# EXM_Relay_Four_-_Rev_A1.net
KiCad netlist of a schematic drawn in EAGLE
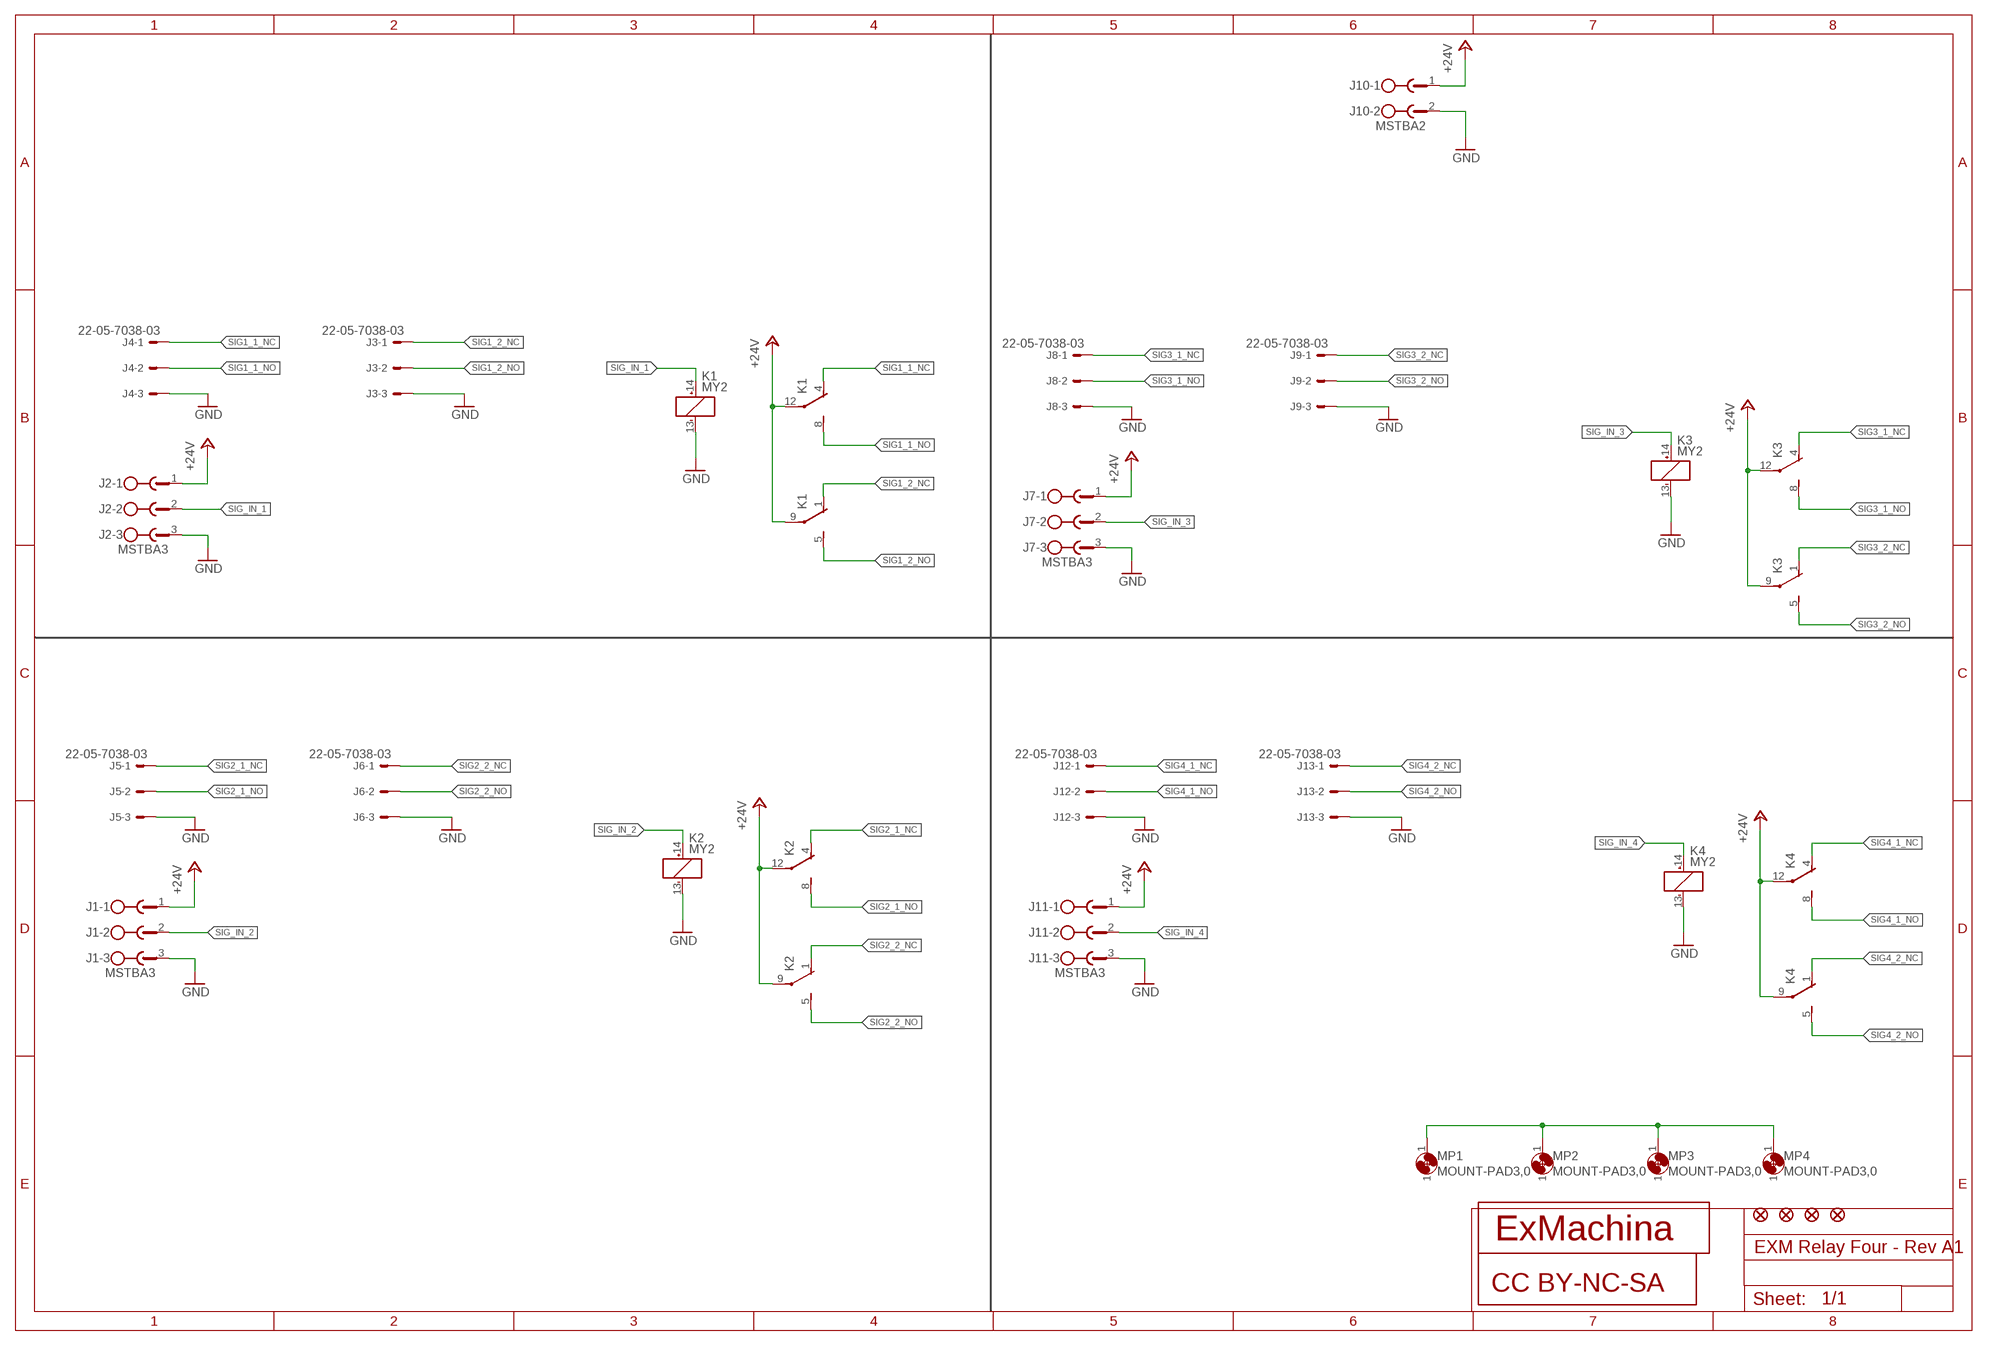
[diagram p0: schematic, sheet 1]

(export (version "E")
  (design (tool "Eeschema 10.0.6"))
  (components
    (comp (ref "CC1")
      (value "CC-BY-NC-SA")
      (footprint "eagle-import:CC-BY-NC-SA")
      (libsource (lib "eagle-import") (part "CC-BY-NC-SA"))
    )
    (comp (ref "J1")
      (value "MSTBA3")
      (footprint "eagle-import:MSTBA3")
      (fields (field (name "MF") "FARNELL") (field (name "MPN") "1757255"))
      (libsource (lib "eagle-import") (part "MSTBA3"))
    )
    (comp (ref "J2")
      (value "MSTBA3")
      (footprint "eagle-import:MSTBA3")
      (fields (field (name "MF") "FARNELL") (field (name "MPN") "1757255"))
      (libsource (lib "eagle-import") (part "MSTBA3"))
    )
    (comp (ref "J3")
      (value "22-05-7038-03")
      (footprint "eagle-import:7395-03")
      (libsource (lib "eagle-import") (part "22-?-0305-7038"))
    )
    (comp (ref "J4")
      (value "22-05-7038-03")
      (footprint "eagle-import:7395-03")
      (libsource (lib "eagle-import") (part "22-?-0305-7038"))
    )
    (comp (ref "J5")
      (value "22-05-7038-03")
      (footprint "eagle-import:7395-03")
      (libsource (lib "eagle-import") (part "22-?-0305-7038"))
    )
    (comp (ref "J6")
      (value "22-05-7038-03")
      (footprint "eagle-import:7395-03")
      (libsource (lib "eagle-import") (part "22-?-0305-7038"))
    )
    (comp (ref "J7")
      (value "MSTBA3")
      (footprint "eagle-import:MSTBA3")
      (fields (field (name "MF") "FARNELL") (field (name "MPN") "1757255"))
      (libsource (lib "eagle-import") (part "MSTBA3"))
    )
    (comp (ref "J8")
      (value "22-05-7038-03")
      (footprint "eagle-import:7395-03")
      (libsource (lib "eagle-import") (part "22-?-0305-7038"))
    )
    (comp (ref "J9")
      (value "22-05-7038-03")
      (footprint "eagle-import:7395-03")
      (libsource (lib "eagle-import") (part "22-?-0305-7038"))
    )
    (comp (ref "J10")
      (value "MSTBA2")
      (footprint "eagle-import:MSTBA2")
      (fields (field (name "MF") "FARNELL") (field (name "MPN") "1757242"))
      (libsource (lib "eagle-import") (part "MSTBA2"))
    )
    (comp (ref "J11")
      (value "MSTBA3")
      (footprint "eagle-import:MSTBA3")
      (fields (field (name "MF") "FARNELL") (field (name "MPN") "1757255"))
      (libsource (lib "eagle-import") (part "MSTBA3"))
    )
    (comp (ref "J12")
      (value "22-05-7038-03")
      (footprint "eagle-import:7395-03")
      (libsource (lib "eagle-import") (part "22-?-0305-7038"))
    )
    (comp (ref "J13")
      (value "22-05-7038-03")
      (footprint "eagle-import:7395-03")
      (libsource (lib "eagle-import") (part "22-?-0305-7038"))
    )
    (comp (ref "JP1")
      (value "FIDUCIAL1X2")
      (footprint "eagle-import:FIDUCIAL-1X2")
      (libsource (lib "eagle-import") (part "FIDUCIAL1X2"))
    )
    (comp (ref "JP2")
      (value "FIDUCIAL1X2")
      (footprint "eagle-import:FIDUCIAL-1X2")
      (libsource (lib "eagle-import") (part "FIDUCIAL1X2"))
    )
    (comp (ref "JP3")
      (value "FIDUCIAL1X2")
      (footprint "eagle-import:FIDUCIAL-1X2")
      (libsource (lib "eagle-import") (part "FIDUCIAL1X2"))
    )
    (comp (ref "JP4")
      (value "FIDUCIAL1X2")
      (footprint "eagle-import:FIDUCIAL-1X2")
      (libsource (lib "eagle-import") (part "FIDUCIAL1X2"))
    )
    (comp (ref "K1")
      (value "MY2")
      (footprint "eagle-import:PY08")
      (libsource (lib "eagle-import") (part "MY2"))
    )
    (comp (ref "K2")
      (value "MY2")
      (footprint "eagle-import:PY08")
      (libsource (lib "eagle-import") (part "MY2"))
    )
    (comp (ref "K3")
      (value "MY2")
      (footprint "eagle-import:PY08")
      (libsource (lib "eagle-import") (part "MY2"))
    )
    (comp (ref "K4")
      (value "MY2")
      (footprint "eagle-import:PY08")
      (libsource (lib "eagle-import") (part "MY2"))
    )
    (comp (ref "MP1")
      (value "MOUNT-PAD3,0")
      (footprint "eagle-import:P3,0")
      (libsource (lib "eagle-import") (part "MOUNT-PAD3,0"))
    )
    (comp (ref "MP2")
      (value "MOUNT-PAD3,0")
      (footprint "eagle-import:P3,0")
      (libsource (lib "eagle-import") (part "MOUNT-PAD3,0"))
    )
    (comp (ref "MP3")
      (value "MOUNT-PAD3,0")
      (footprint "eagle-import:P3,0")
      (libsource (lib "eagle-import") (part "MOUNT-PAD3,0"))
    )
    (comp (ref "MP4")
      (value "MOUNT-PAD3,0")
      (footprint "eagle-import:P3,0")
      (libsource (lib "eagle-import") (part "MOUNT-PAD3,0"))
    )
    (comp (ref "T1")
      (value "EXMACHINA-LOGO-NAME")
      (footprint "eagle-import:EXM-LOGO-BASELINE")
      (libsource (lib "eagle-import") (part "EXMACHINA-LOGO-NAME"))
    )
  )
  (nets
    (net (code "1") (name "+24V") (class "Default")
      (node (ref "J1") (pin "1") (pinfunction "1_1") (pintype "passive"))
      (node (ref "J10") (pin "1") (pinfunction "1_1") (pintype "passive"))
      (node (ref "J11") (pin "1") (pinfunction "1_1") (pintype "passive"))
      (node (ref "J2") (pin "1") (pinfunction "1_1") (pintype "passive"))
      (node (ref "J7") (pin "1") (pinfunction "1_1") (pintype "passive"))
      (node (ref "K1") (pin "12") (pinfunction "C_12") (pintype "passive"))
      (node (ref "K1") (pin "9") (pinfunction "C_9") (pintype "passive"))
      (node (ref "K2") (pin "12") (pinfunction "C_12") (pintype "passive"))
      (node (ref "K2") (pin "9") (pinfunction "C_9") (pintype "passive"))
      (node (ref "K3") (pin "12") (pinfunction "C_12") (pintype "passive"))
      (node (ref "K3") (pin "9") (pinfunction "C_9") (pintype "passive"))
      (node (ref "K4") (pin "12") (pinfunction "C_12") (pintype "passive"))
      (node (ref "K4") (pin "9") (pinfunction "C_9") (pintype "passive"))
    )
    (net (code "2") (name "GND") (class "Default")
      (node (ref "J1") (pin "3") (pinfunction "1_3") (pintype "passive"))
      (node (ref "J10") (pin "2") (pinfunction "1_2") (pintype "passive"))
      (node (ref "J11") (pin "3") (pinfunction "1_3") (pintype "passive"))
      (node (ref "J12") (pin "3") (pinfunction "S_3") (pintype "passive"))
      (node (ref "J13") (pin "3") (pinfunction "S_3") (pintype "passive"))
      (node (ref "J2") (pin "3") (pinfunction "1_3") (pintype "passive"))
      (node (ref "J3") (pin "3") (pinfunction "S_3") (pintype "passive"))
      (node (ref "J4") (pin "3") (pinfunction "S_3") (pintype "passive"))
      (node (ref "J5") (pin "3") (pinfunction "S_3") (pintype "passive"))
      (node (ref "J6") (pin "3") (pinfunction "S_3") (pintype "passive"))
      (node (ref "J7") (pin "3") (pinfunction "1_3") (pintype "passive"))
      (node (ref "J8") (pin "3") (pinfunction "S_3") (pintype "passive"))
      (node (ref "J9") (pin "3") (pinfunction "S_3") (pintype "passive"))
      (node (ref "K1") (pin "13") (pinfunction "-_13") (pintype "passive"))
      (node (ref "K2") (pin "13") (pinfunction "-_13") (pintype "passive"))
      (node (ref "K3") (pin "13") (pinfunction "-_13") (pintype "passive"))
      (node (ref "K4") (pin "13") (pinfunction "-_13") (pintype "passive"))
    )
    (net (code "3") (name "MOUNT-PAD3,0") (class "Default")
      (node (ref "MP1") (pin "1") (pinfunction "1_1") (pintype "power_in"))
      (node (ref "MP2") (pin "1") (pinfunction "1_1") (pintype "power_in"))
      (node (ref "MP3") (pin "1") (pinfunction "1_1") (pintype "power_in"))
      (node (ref "MP4") (pin "1") (pinfunction "1_1") (pintype "power_in"))
    )
    (net (code "4") (name "SIG1_1_NC") (class "Default")
      (node (ref "J4") (pin "1") (pinfunction "S_1") (pintype "passive"))
      (node (ref "K1") (pin "4") (pinfunction "NC_4") (pintype "passive"))
    )
    (net (code "5") (name "SIG1_1_NO") (class "Default")
      (node (ref "J4") (pin "2") (pinfunction "S_2") (pintype "passive"))
      (node (ref "K1") (pin "8") (pinfunction "NO_8") (pintype "passive"))
    )
    (net (code "6") (name "SIG1_2_NC") (class "Default")
      (node (ref "J3") (pin "1") (pinfunction "S_1") (pintype "passive"))
      (node (ref "K1") (pin "1") (pinfunction "NC_1") (pintype "passive"))
    )
    (net (code "7") (name "SIG1_2_NO") (class "Default")
      (node (ref "J3") (pin "2") (pinfunction "S_2") (pintype "passive"))
      (node (ref "K1") (pin "5") (pinfunction "NO_5") (pintype "passive"))
    )
    (net (code "8") (name "SIG2_1_NC") (class "Default")
      (node (ref "J5") (pin "1") (pinfunction "S_1") (pintype "passive"))
      (node (ref "K2") (pin "4") (pinfunction "NC_4") (pintype "passive"))
    )
    (net (code "9") (name "SIG2_1_NO") (class "Default")
      (node (ref "J5") (pin "2") (pinfunction "S_2") (pintype "passive"))
      (node (ref "K2") (pin "8") (pinfunction "NO_8") (pintype "passive"))
    )
    (net (code "10") (name "SIG2_2_NC") (class "Default")
      (node (ref "J6") (pin "1") (pinfunction "S_1") (pintype "passive"))
      (node (ref "K2") (pin "1") (pinfunction "NC_1") (pintype "passive"))
    )
    (net (code "11") (name "SIG2_2_NO") (class "Default")
      (node (ref "J6") (pin "2") (pinfunction "S_2") (pintype "passive"))
      (node (ref "K2") (pin "5") (pinfunction "NO_5") (pintype "passive"))
    )
    (net (code "12") (name "SIG3_1_NC") (class "Default")
      (node (ref "J8") (pin "1") (pinfunction "S_1") (pintype "passive"))
      (node (ref "K3") (pin "4") (pinfunction "NC_4") (pintype "passive"))
    )
    (net (code "13") (name "SIG3_1_NO") (class "Default")
      (node (ref "J8") (pin "2") (pinfunction "S_2") (pintype "passive"))
      (node (ref "K3") (pin "8") (pinfunction "NO_8") (pintype "passive"))
    )
    (net (code "14") (name "SIG3_2_NC") (class "Default")
      (node (ref "J9") (pin "1") (pinfunction "S_1") (pintype "passive"))
      (node (ref "K3") (pin "1") (pinfunction "NC_1") (pintype "passive"))
    )
    (net (code "15") (name "SIG3_2_NO") (class "Default")
      (node (ref "J9") (pin "2") (pinfunction "S_2") (pintype "passive"))
      (node (ref "K3") (pin "5") (pinfunction "NO_5") (pintype "passive"))
    )
    (net (code "16") (name "SIG4_1_NC") (class "Default")
      (node (ref "J12") (pin "1") (pinfunction "S_1") (pintype "passive"))
      (node (ref "K4") (pin "4") (pinfunction "NC_4") (pintype "passive"))
    )
    (net (code "17") (name "SIG4_1_NO") (class "Default")
      (node (ref "J12") (pin "2") (pinfunction "S_2") (pintype "passive"))
      (node (ref "K4") (pin "8") (pinfunction "NO_8") (pintype "passive"))
    )
    (net (code "18") (name "SIG4_2_NC") (class "Default")
      (node (ref "J13") (pin "1") (pinfunction "S_1") (pintype "passive"))
      (node (ref "K4") (pin "1") (pinfunction "NC_1") (pintype "passive"))
    )
    (net (code "19") (name "SIG4_2_NO") (class "Default")
      (node (ref "J13") (pin "2") (pinfunction "S_2") (pintype "passive"))
      (node (ref "K4") (pin "5") (pinfunction "NO_5") (pintype "passive"))
    )
    (net (code "20") (name "SIG_IN_1") (class "Default")
      (node (ref "J2") (pin "2") (pinfunction "1_2") (pintype "passive"))
      (node (ref "K1") (pin "14") (pinfunction "+_14") (pintype "passive"))
    )
    (net (code "21") (name "SIG_IN_2") (class "Default")
      (node (ref "J1") (pin "2") (pinfunction "1_2") (pintype "passive"))
      (node (ref "K2") (pin "14") (pinfunction "+_14") (pintype "passive"))
    )
    (net (code "22") (name "SIG_IN_3") (class "Default")
      (node (ref "J7") (pin "2") (pinfunction "1_2") (pintype "passive"))
      (node (ref "K3") (pin "14") (pinfunction "+_14") (pintype "passive"))
    )
    (net (code "23") (name "SIG_IN_4") (class "Default")
      (node (ref "J11") (pin "2") (pinfunction "1_2") (pintype "passive"))
      (node (ref "K4") (pin "14") (pinfunction "+_14") (pintype "passive"))
    )
  )
)
